# Sheet1.net
KiCad netlist of a schematic drawn in Altium Designer
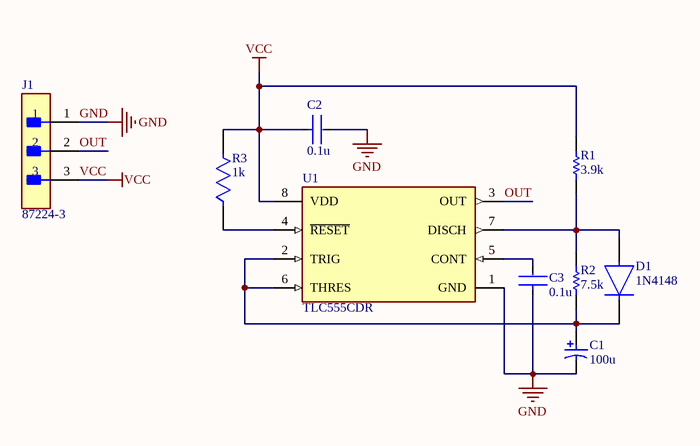
[diagram p0: Sheet1.SchDoc]

(export (version "E")
  (design (tool "Eeschema 10.0.6"))
  (components
    (comp (ref "C1")
      (value "100u")
      (footprint "CAPPR60-350-1150X800X1300")
      (description "Aluminum Electrolytic Capacitor, 100 uF, +/- 20%, 35 V, -55 to 105 degC, 2-Pin THD, RoHS, Bulk")
      (fields (field (name "TOLERANCE") "-20,+20%") (field (name "MANUFACTURER") "Nichicon"))
      (libsource (lib "UPW1V101MPD") (part "CMP-2000-07363-1"))
    )
    (comp (ref "C2")
      (value "0.1u")
      (footprint "FP-CC0805-0_85-IPC_C")
      (description "CAP CER 0.1UF 25V X7R 0805")
      (fields (field (name "MANUFACTURER PART NUMBER") "CC0805KRX7R8BB104") (field (name "TOLERANCE") "0.1"))
      (libsource (lib "C0805C104K3RACTU") (part "CMP-1036-04410-2"))
    )
    (comp (ref "C3")
      (value "0.1u")
      (footprint "FP-CC0805-0_85-IPC_C")
      (description "CAP CER 0.1UF 25V X7R 0805")
      (fields (field (name "MANUFACTURER PART NUMBER") "CC0805KRX7R8BB104") (field (name "TOLERANCE") "0.1"))
      (libsource (lib "C0805C104K3RACTU") (part "CMP-1036-04410-2"))
    )
    (comp (ref "D1")
      (value "1N4148")
      (footprint "FP-017AG-MFG")
      (description "DIODE GEN PURP 100V 200MA DO35")
      (fields (field (name "VOLTAGE") "100V"))
      (libsource (lib "1N4148") (part "CMP-07163-000046-1"))
    )
    (comp (ref "J1")
      (value "87224-3")
      (footprint "FP-87224-3-MFG")
      (description "CONN HEADER VERT 3POS 2.54MM")
      (libsource (lib "87224-3") (part "CMP-2000-05697-2"))
    )
    (comp (ref "R1")
      (value "3.9k")
      (footprint "RESC2013X70X40NL20T20")
      (fields (field (name "MANUFACTURER") "Panasonic") (field (name "PART NUMBER") "ERJ6ENF3901V"))
      (libsource (lib "ERJ-6ENF3901V") (part "CMP-2001-00541-1"))
    )
    (comp (ref "R2")
      (value "7.5k")
      (footprint "RESC2013X70X40NL20T20")
      (fields (field (name "MANUFACTURER") "Panasonic") (field (name "PART NUMBER") "ERJ-6ENF7501V"))
      (libsource (lib "ERJ-6ENF7501V") (part "CMP-2001-00289-1"))
    )
    (comp (ref "R3")
      (value "1k")
      (footprint "FP-RC2012-IPC_B")
      (description "Res Thick Film 0805 1kΩ 1% 0.125W ±100ppm/°C Molded SMD T/R")
      (fields (field (name "TOLERANCE") "1%"))
      (libsource (lib "RC2012F102CS") (part "CMP-13261-003265-1"))
    )
    (comp (ref "U1")
      (value "TLC555CDR")
      (footprint "FP-D0008A-IPC_B")
      (description "IC OSC SGL TIMER 2.1MHZ 8-SOIC")
      (libsource (lib "TLC555CDR") (part "CMP-04857-000001-1"))
    )
  )
  (nets
    (net (code "1") (name "/OUT") (class "Default")
      (node (ref "J1") (pin "2") (pinfunction "2_2") (pintype "passive"))
      (node (ref "U1") (pin "3") (pinfunction "OUT_3") (pintype "output"))
    )
    (net (code "2") (name "GND") (class "Default")
      (node (ref "C1") (pin "2") (pinfunction "2_2") (pintype "passive"))
      (node (ref "C2") (pin "2") (pinfunction "2_2") (pintype "passive"))
      (node (ref "C3") (pin "1") (pinfunction "1_1") (pintype "passive"))
      (node (ref "J1") (pin "1") (pinfunction "1_1") (pintype "passive"))
      (node (ref "U1") (pin "1") (pinfunction "GND_1") (pintype "power_in"))
    )
    (net (code "3") (name "Net-(D1-A)") (class "Default")
      (node (ref "D1") (pin "2") (pinfunction "A_2") (pintype "passive"))
      (node (ref "R1") (pin "1") (pinfunction "1_1") (pintype "passive"))
      (node (ref "R2") (pin "2") (pinfunction "2_2") (pintype "passive"))
      (node (ref "U1") (pin "7") (pinfunction "DISCH_7") (pintype "output"))
    )
    (net (code "4") (name "Net-(D1-C)") (class "Default")
      (node (ref "C1") (pin "1") (pinfunction "1_1") (pintype "passive"))
      (node (ref "D1") (pin "1") (pinfunction "C_1") (pintype "passive"))
      (node (ref "R2") (pin "1") (pinfunction "1_1") (pintype "passive"))
      (node (ref "U1") (pin "2") (pinfunction "TRIG_2") (pintype "input"))
      (node (ref "U1") (pin "6") (pinfunction "THRES_6") (pintype "input"))
    )
    (net (code "5") (name "Net-(U1-CONT)") (class "Default")
      (node (ref "C3") (pin "2") (pinfunction "2_2") (pintype "passive"))
      (node (ref "U1") (pin "5") (pinfunction "CONT_5") (pintype "input"))
    )
    (net (code "6") (name "Net-(U1-~{RESET})") (class "Default")
      (node (ref "R3") (pin "1") (pinfunction "1_1") (pintype "passive"))
      (node (ref "U1") (pin "4") (pinfunction "~{RESET}_4") (pintype "input"))
    )
    (net (code "7") (name "VCC") (class "Default")
      (node (ref "C2") (pin "1") (pinfunction "1_1") (pintype "passive"))
      (node (ref "J1") (pin "3") (pinfunction "3_3") (pintype "passive"))
      (node (ref "R1") (pin "2") (pinfunction "2_2") (pintype "passive"))
      (node (ref "R3") (pin "2") (pinfunction "2_2") (pintype "passive"))
      (node (ref "U1") (pin "8") (pinfunction "VDD_8") (pintype "power_in"))
    )
  )
)
